# Buttons.net
KiCad netlist of a schematic drawn in EAGLE
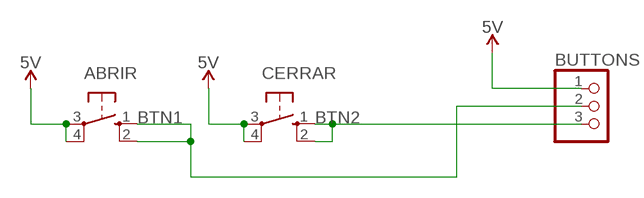
[diagram p0: schematic, sheet 1]

(export (version "E")
  (design (tool "Eeschema 10.0.6"))
  (components
    (comp (ref "ABRIR")
      (value "10-XX")
      (footprint "eagle-import:B3F-10XX")
      (fields (field (name "MPN") "B3F-1000"))
      (libsource (lib "eagle-import") (part "10-XX"))
    )
    (comp (ref "BUTTONS")
      (value "PINHD-1X3")
      (footprint "eagle-import:1X03")
      (libsource (lib "eagle-import") (part "PINHD-1X3"))
    )
    (comp (ref "CERRAR")
      (value "10-XX")
      (footprint "eagle-import:B3F-10XX")
      (fields (field (name "MPN") "B3F-1000"))
      (libsource (lib "eagle-import") (part "10-XX"))
    )
  )
  (nets
    (net (code "1") (name "/BTN1") (class "Default")
      (node (ref "ABRIR") (pin "1") (pinfunction "S_1") (pintype "passive"))
      (node (ref "ABRIR") (pin "2") (pinfunction "S1_2") (pintype "passive"))
      (node (ref "BUTTONS") (pin "2") (pinfunction "2_2") (pintype "passive"))
    )
    (net (code "2") (name "/BTN2") (class "Default")
      (node (ref "BUTTONS") (pin "3") (pinfunction "3_3") (pintype "passive"))
      (node (ref "CERRAR") (pin "1") (pinfunction "S_1") (pintype "passive"))
      (node (ref "CERRAR") (pin "2") (pinfunction "S1_2") (pintype "passive"))
    )
    (net (code "3") (name "5V") (class "Default")
      (node (ref "ABRIR") (pin "3") (pinfunction "P_3") (pintype "passive"))
      (node (ref "ABRIR") (pin "4") (pinfunction "P1_4") (pintype "passive"))
      (node (ref "BUTTONS") (pin "1") (pinfunction "1_1") (pintype "passive"))
      (node (ref "CERRAR") (pin "3") (pinfunction "P_3") (pintype "passive"))
      (node (ref "CERRAR") (pin "4") (pinfunction "P1_4") (pintype "passive"))
    )
  )
)
